# spaceloop_controller.net
KiCad netlist of a schematic drawn in EAGLE
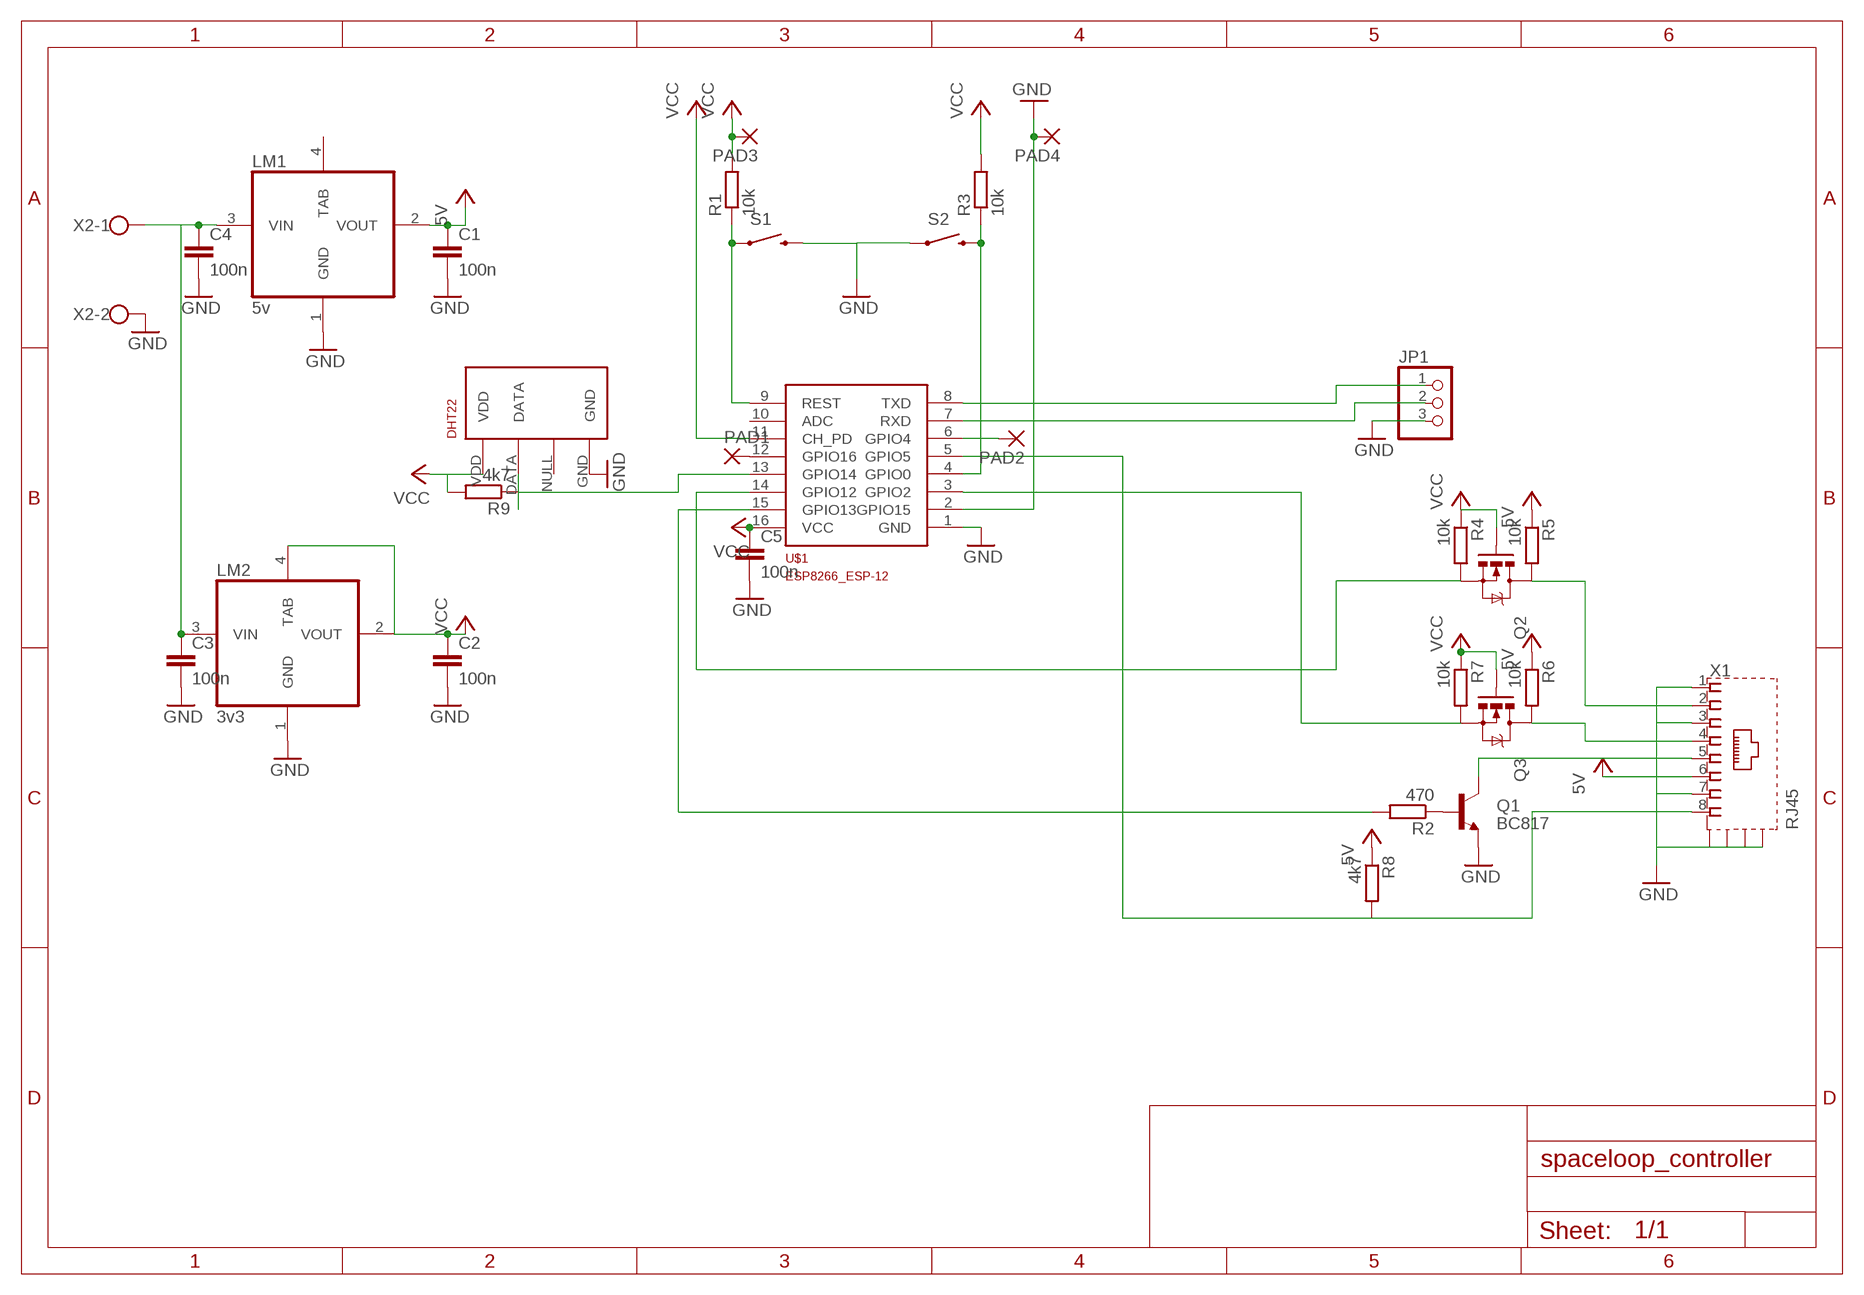
[diagram p0: schematic, sheet 1]

(export (version "E")
  (design (tool "Eeschema 10.0.6"))
  (components
    (comp (ref "C1")
      (value "100n")
      (footprint "eagle-import:C0805")
      (libsource (lib "eagle-import") (part "C-EUC0805"))
    )
    (comp (ref "C2")
      (value "100n")
      (footprint "eagle-import:C0805")
      (libsource (lib "eagle-import") (part "C-EUC0805"))
    )
    (comp (ref "C3")
      (value "100n")
      (footprint "eagle-import:C0805")
      (libsource (lib "eagle-import") (part "C-EUC0805"))
    )
    (comp (ref "C4")
      (value "100n")
      (footprint "eagle-import:C0805")
      (libsource (lib "eagle-import") (part "C-EUC0805"))
    )
    (comp (ref "C5")
      (value "100n")
      (footprint "eagle-import:C0805")
      (libsource (lib "eagle-import") (part "C-EUC0805"))
    )
    (comp (ref "DHT22")
      (value "RHT03_DHT-22_AM2302WIRED")
      (footprint "eagle-import:AM2302")
      (libsource (lib "eagle-import") (part "RHT03_DHT-22_AM2302WIRED"))
    )
    (comp (ref "JP1")
      (value "PINHD-1X3")
      (footprint "eagle-import:1X03")
      (libsource (lib "eagle-import") (part "PINHD-1X3"))
    )
    (comp (ref "LM1")
      (value "5v")
      (footprint "eagle-import:SOT223")
      (libsource (lib "eagle-import") (part "REG1117"))
    )
    (comp (ref "LM2")
      (value "3v3")
      (footprint "eagle-import:SOT223")
      (libsource (lib "eagle-import") (part "REG1117"))
    )
    (comp (ref "PAD1")
      (value "SMD2")
      (footprint "eagle-import:SMD1,27-2,54")
      (libsource (lib "eagle-import") (part "SMD2"))
    )
    (comp (ref "PAD2")
      (value "SMD2")
      (footprint "eagle-import:SMD1,27-2,54")
      (libsource (lib "eagle-import") (part "SMD2"))
    )
    (comp (ref "PAD3")
      (value "SMD2")
      (footprint "eagle-import:SMD1,27-2,54")
      (libsource (lib "eagle-import") (part "SMD2"))
    )
    (comp (ref "PAD4")
      (value "SMD2")
      (footprint "eagle-import:SMD1,27-2,54")
      (libsource (lib "eagle-import") (part "SMD2"))
    )
    (comp (ref "Q1")
      (value "BC817")
      (footprint "eagle-import:SOT23-3")
      (libsource (lib "eagle-import") (part "TRANSISTOR_NPNSOT23-3"))
    )
    (comp (ref "Q2")
      (value "BSS138")
      (footprint "eagle-import:SOT23-3")
      (libsource (lib "eagle-import") (part "MOSFET-NCHANNELBSS138"))
    )
    (comp (ref "Q3")
      (value "BSS138")
      (footprint "eagle-import:SOT23-3")
      (libsource (lib "eagle-import") (part "MOSFET-NCHANNELBSS138"))
    )
    (comp (ref "R1")
      (value "10k")
      (footprint "eagle-import:R0805")
      (libsource (lib "eagle-import") (part "R-EU_R0805"))
    )
    (comp (ref "R2")
      (value "470")
      (footprint "eagle-import:R0805")
      (libsource (lib "eagle-import") (part "R-EU_R0805"))
    )
    (comp (ref "R3")
      (value "10k")
      (footprint "eagle-import:R0805")
      (libsource (lib "eagle-import") (part "R-EU_R0805"))
    )
    (comp (ref "R4")
      (value "10k")
      (footprint "eagle-import:R0805")
      (libsource (lib "eagle-import") (part "R-EU_R0805"))
    )
    (comp (ref "R5")
      (value "10k")
      (footprint "eagle-import:R0805")
      (libsource (lib "eagle-import") (part "R-EU_R0805"))
    )
    (comp (ref "R6")
      (value "10k")
      (footprint "eagle-import:R0805")
      (libsource (lib "eagle-import") (part "R-EU_R0805"))
    )
    (comp (ref "R7")
      (value "10k")
      (footprint "eagle-import:R0805")
      (libsource (lib "eagle-import") (part "R-EU_R0805"))
    )
    (comp (ref "R8")
      (value "4k7")
      (footprint "eagle-import:R0805")
      (libsource (lib "eagle-import") (part "R-EU_R0805"))
    )
    (comp (ref "R9")
      (value "4k7")
      (footprint "eagle-import:R0805")
      (libsource (lib "eagle-import") (part "R-EU_R0805"))
    )
    (comp (ref "S1")
      (value "SWITCH-MOMENTARY-2SMD-1101NE")
      (footprint "eagle-import:TACTILE-SWITCH-1101NE")
      (libsource (lib "eagle-import") (part "SWITCH-MOMENTARY-2SMD-1101NE"))
    )
    (comp (ref "S2")
      (value "SWITCH-MOMENTARY-2SMD-1101NE")
      (footprint "eagle-import:TACTILE-SWITCH-1101NE")
      (libsource (lib "eagle-import") (part "SWITCH-MOMENTARY-2SMD-1101NE"))
    )
    (comp (ref "U$1")
      (value "ESP8266_ESP-12")
      (footprint "eagle-import:ESP8266-ESP12")
      (libsource (lib "eagle-import") (part "ESP8266_ESP-12"))
    )
    (comp (ref "X1")
      (value "RJ45")
      (footprint "eagle-import:RJ45-SHIELD2")
      (fields (field (name "MPN") "RJ45-6L2-B"))
      (libsource (lib "eagle-import") (part "RJ452-B-6L"))
    )
    (comp (ref "X2")
      (value "W237-102")
      (footprint "eagle-import:W237-102")
      (fields (field (name "MPN") "237-102"))
      (libsource (lib "eagle-import") (part "W237-102"))
    )
  )
  (nets
    (net (code "1") (name "5V") (class "Default")
      (node (ref "C1") (pin "1") (pinfunction "1_1") (pintype "passive"))
      (node (ref "LM1") (pin "2") (pinfunction "VOUT_2") (pintype "output"))
      (node (ref "R5") (pin "1") (pinfunction "1_1") (pintype "passive"))
      (node (ref "R6") (pin "1") (pinfunction "1_1") (pintype "passive"))
      (node (ref "R8") (pin "1") (pinfunction "1_1") (pintype "passive"))
      (node (ref "X1") (pin "6") (pinfunction "6_6") (pintype "passive"))
    )
    (net (code "2") (name "GND") (class "Default")
      (node (ref "C1") (pin "2") (pinfunction "2_2") (pintype "passive"))
      (node (ref "C2") (pin "2") (pinfunction "2_2") (pintype "passive"))
      (node (ref "C3") (pin "2") (pinfunction "2_2") (pintype "passive"))
      (node (ref "C4") (pin "2") (pinfunction "2_2") (pintype "passive"))
      (node (ref "C5") (pin "2") (pinfunction "2_2") (pintype "passive"))
      (node (ref "DHT22") (pin "GND") (pinfunction "GND_GND") (pintype "power_in"))
      (node (ref "JP1") (pin "3") (pinfunction "3_3") (pintype "passive"))
      (node (ref "LM1") (pin "1") (pinfunction "GND_1") (pintype "power_in"))
      (node (ref "LM2") (pin "1") (pinfunction "GND_1") (pintype "power_in"))
      (node (ref "PAD4") (pin "1") (pinfunction "P_1") (pintype "passive"))
      (node (ref "Q1") (pin "2") (pinfunction "E_2") (pintype "passive"))
      (node (ref "S1") (pin "2") (pinfunction "2_2") (pintype "passive"))
      (node (ref "S2") (pin "1") (pinfunction "1_1") (pintype "passive"))
      (node (ref "U$1") (pin "1") (pinfunction "GND_1") (pintype "bidirectional"))
      (node (ref "U$1") (pin "2") (pinfunction "GPIO15_2") (pintype "bidirectional"))
      (node (ref "X1") (pin "1") (pinfunction "1_1") (pintype "passive"))
      (node (ref "X1") (pin "3") (pinfunction "3_3") (pintype "passive"))
      (node (ref "X1") (pin "7") (pinfunction "7_7") (pintype "passive"))
      (node (ref "X1") (pin "S1") (pinfunction "S_S1") (pintype "passive"))
      (node (ref "X1") (pin "S2") (pinfunction "S_S2") (pintype "passive"))
      (node (ref "X1") (pin "S3") (pinfunction "S_S3") (pintype "passive"))
      (node (ref "X1") (pin "S4") (pinfunction "S_S4") (pintype "passive"))
      (node (ref "X2") (pin "2") (pinfunction "KL_2") (pintype "passive"))
    )
    (net (code "3") (name "Net-(LM1-VIN)") (class "Default")
      (node (ref "C3") (pin "1") (pinfunction "1_1") (pintype "passive"))
      (node (ref "C4") (pin "1") (pinfunction "1_1") (pintype "passive"))
      (node (ref "LM1") (pin "3") (pinfunction "VIN_3") (pintype "input"))
      (node (ref "LM2") (pin "3") (pinfunction "VIN_3") (pintype "input"))
      (node (ref "X2") (pin "1") (pinfunction "KL_1") (pintype "passive"))
    )
    (net (code "4") (name "Net-(PAD1-P)") (class "Default")
      (node (ref "PAD1") (pin "1") (pinfunction "P_1") (pintype "passive"))
      (node (ref "U$1") (pin "12") (pinfunction "GPIO16_12") (pintype "bidirectional"))
    )
    (net (code "5") (name "Net-(PAD2-P)") (class "Default")
      (node (ref "PAD2") (pin "1") (pinfunction "P_1") (pintype "passive"))
      (node (ref "U$1") (pin "6") (pinfunction "GPIO4_6") (pintype "bidirectional"))
    )
    (net (code "6") (name "Net-(Q1-B)") (class "Default")
      (node (ref "Q1") (pin "1") (pinfunction "B_1") (pintype "passive"))
      (node (ref "R2") (pin "1") (pinfunction "1_1") (pintype "passive"))
    )
    (net (code "7") (name "Net-(Q1-C)") (class "Default")
      (node (ref "Q1") (pin "3") (pinfunction "C_3") (pintype "passive"))
      (node (ref "X1") (pin "5") (pinfunction "5_5") (pintype "passive"))
    )
    (net (code "8") (name "Net-(Q2-D)") (class "Default")
      (node (ref "Q2") (pin "3") (pinfunction "D_3") (pintype "passive"))
      (node (ref "R5") (pin "2") (pinfunction "2_2") (pintype "passive"))
      (node (ref "X1") (pin "2") (pinfunction "2_2") (pintype "passive"))
    )
    (net (code "9") (name "Net-(Q2-S)") (class "Default")
      (node (ref "Q2") (pin "2") (pinfunction "S_2") (pintype "passive"))
      (node (ref "R4") (pin "2") (pinfunction "2_2") (pintype "passive"))
      (node (ref "U$1") (pin "14") (pinfunction "GPIO12_14") (pintype "bidirectional"))
    )
    (net (code "10") (name "Net-(Q3-D)") (class "Default")
      (node (ref "Q3") (pin "3") (pinfunction "D_3") (pintype "passive"))
      (node (ref "R6") (pin "2") (pinfunction "2_2") (pintype "passive"))
      (node (ref "X1") (pin "4") (pinfunction "4_4") (pintype "passive"))
    )
    (net (code "11") (name "Net-(Q3-S)") (class "Default")
      (node (ref "Q3") (pin "2") (pinfunction "S_2") (pintype "passive"))
      (node (ref "R7") (pin "2") (pinfunction "2_2") (pintype "passive"))
      (node (ref "U$1") (pin "3") (pinfunction "GPIO2_3") (pintype "bidirectional"))
    )
    (net (code "12") (name "Net-(U$1-GPIO0)") (class "Default")
      (node (ref "R3") (pin "1") (pinfunction "1_1") (pintype "passive"))
      (node (ref "S2") (pin "2") (pinfunction "2_2") (pintype "passive"))
      (node (ref "U$1") (pin "4") (pinfunction "GPIO0_4") (pintype "bidirectional"))
    )
    (net (code "13") (name "Net-(U$1-GPIO5)") (class "Default")
      (node (ref "R8") (pin "2") (pinfunction "2_2") (pintype "passive"))
      (node (ref "U$1") (pin "5") (pinfunction "GPIO5_5") (pintype "bidirectional"))
      (node (ref "X1") (pin "8") (pinfunction "8_8") (pintype "passive"))
    )
    (net (code "14") (name "Net-(U$1-GPIO13)") (class "Default")
      (node (ref "R2") (pin "2") (pinfunction "2_2") (pintype "passive"))
      (node (ref "U$1") (pin "15") (pinfunction "GPIO13_15") (pintype "bidirectional"))
    )
    (net (code "15") (name "Net-(U$1-GPIO14)") (class "Default")
      (node (ref "DHT22") (pin "DATA") (pinfunction "DATA_DATA") (pintype "bidirectional"))
      (node (ref "R9") (pin "1") (pinfunction "1_1") (pintype "passive"))
      (node (ref "U$1") (pin "13") (pinfunction "GPIO14_13") (pintype "bidirectional"))
    )
    (net (code "16") (name "Net-(U$1-REST)") (class "Default")
      (node (ref "R1") (pin "1") (pinfunction "1_1") (pintype "passive"))
      (node (ref "S1") (pin "1") (pinfunction "1_1") (pintype "passive"))
      (node (ref "U$1") (pin "9") (pinfunction "REST_9") (pintype "bidirectional"))
    )
    (net (code "17") (name "Net-(U$1-RXD)") (class "Default")
      (node (ref "JP1") (pin "2") (pinfunction "2_2") (pintype "passive"))
      (node (ref "U$1") (pin "7") (pinfunction "RXD_7") (pintype "bidirectional"))
    )
    (net (code "18") (name "Net-(U$1-TXD)") (class "Default")
      (node (ref "JP1") (pin "1") (pinfunction "1_1") (pintype "passive"))
      (node (ref "U$1") (pin "8") (pinfunction "TXD_8") (pintype "bidirectional"))
    )
    (net (code "19") (name "VCC") (class "Default")
      (node (ref "C2") (pin "1") (pinfunction "1_1") (pintype "passive"))
      (node (ref "C5") (pin "1") (pinfunction "1_1") (pintype "passive"))
      (node (ref "DHT22") (pin "VDD") (pinfunction "VDD_VDD") (pintype "power_in"))
      (node (ref "LM2") (pin "2") (pinfunction "VOUT_2") (pintype "output"))
      (node (ref "LM2") (pin "4") (pinfunction "TAB_4") (pintype "bidirectional"))
      (node (ref "PAD3") (pin "1") (pinfunction "P_1") (pintype "passive"))
      (node (ref "Q2") (pin "1") (pinfunction "G_1") (pintype "passive"))
      (node (ref "Q3") (pin "1") (pinfunction "G_1") (pintype "passive"))
      (node (ref "R1") (pin "2") (pinfunction "2_2") (pintype "passive"))
      (node (ref "R3") (pin "2") (pinfunction "2_2") (pintype "passive"))
      (node (ref "R4") (pin "1") (pinfunction "1_1") (pintype "passive"))
      (node (ref "R7") (pin "1") (pinfunction "1_1") (pintype "passive"))
      (node (ref "R9") (pin "2") (pinfunction "2_2") (pintype "passive"))
      (node (ref "U$1") (pin "11") (pinfunction "CH_PD_11") (pintype "bidirectional"))
      (node (ref "U$1") (pin "16") (pinfunction "VCC_16") (pintype "bidirectional"))
    )
    (net (code "20") (name "unconnected-(DHT22-PadNULL)") (class "Default")
      (node (ref "DHT22") (pin "NULL") (pinfunction "NULL_NULL") (pintype "no_connect"))
    )
    (net (code "21") (name "unconnected-(LM1-TAB-Pad4)") (class "Default")
      (node (ref "LM1") (pin "4") (pinfunction "TAB_4") (pintype "bidirectional"))
    )
    (net (code "22") (name "unconnected-(U$1-ADC-Pad10)") (class "Default")
      (node (ref "U$1") (pin "10") (pinfunction "ADC_10") (pintype "bidirectional"))
    )
  )
)
